# Kajtu_-DSP_digital_in.net
KiCad netlist of a schematic drawn in Altium Designer
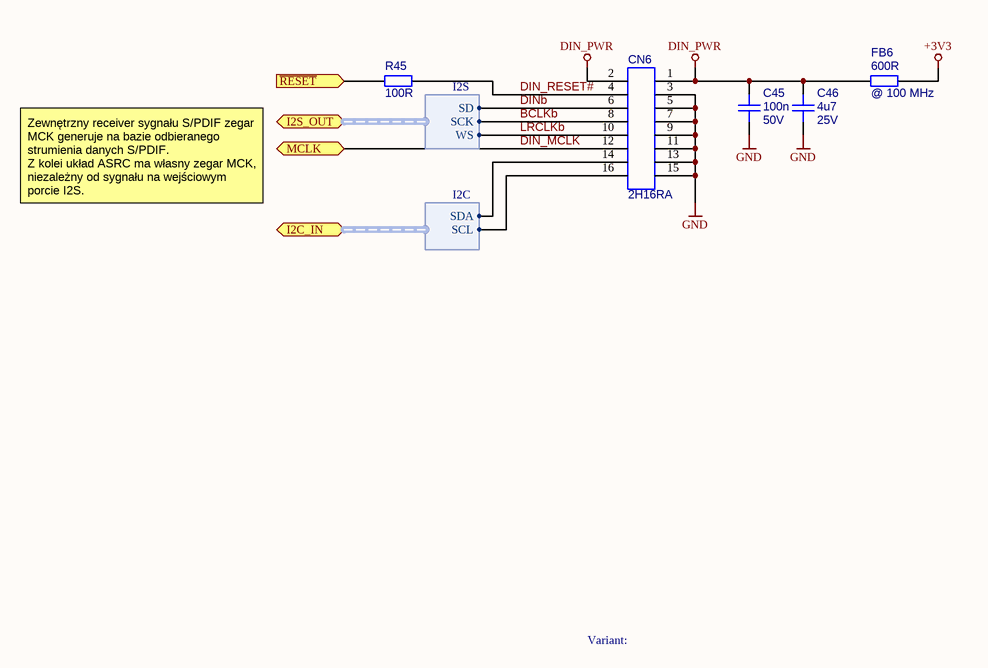
[diagram p0: Kajtuś-DSP_digital_in.SchDoc]

(export (version "E")
  (design (tool "Eeschema 10.0.6"))
  (components
    (comp (ref "C45")
      (value "100n")
      (footprint "C_0603_MA")
      (description "Kondensator ceramiczny SMD")
      (fields (field (name "PART NUMBER") "C_0603_100n_50V_X7R") (field (name "VOLTAGE") "50V"))
      (libsource (lib "AD_ostry_intlib") (part "C_0603_100n_50V_X7R"))
    )
    (comp (ref "C46")
      (value "4u7")
      (footprint "C_1206_MA")
      (description "Kondensator ceramiczny SMD")
      (fields
        (field (name "PART NUMBER") "C_1206_4u7_25V_X7R")
        (field (name "MANUFACTURER") "AVX, KEMET")
        (field (name "VOLTAGE") "25V")
      )
      (libsource (lib "AD_ostry_intlib") (part "C_1206_4u7_25V_X7R"))
    )
    (comp (ref "CN6")
      (value "2H16RA")
      (footprint "CN_2H16RA_WE_WR-PHD_61301621021")
      (description "Listwa kołkowa")
      (fields (field (name "PART NUMBER") "CN_2H16RA") (field (name "MANUFACTURER") "Ninigi"))
      (libsource (lib "AD_ostry_intlib") (part "CN_2H16RA"))
    )
    (comp (ref "FB6")
      (value "600R")
      (footprint "R_0603_MA")
      (description "Koralik ferrytowy")
      (fields
        (field (name "MANUFACTURER") "Yageo")
        (field (name "PART NUMBER") "FB_0603_PBY160808T-601Y_600R_1A")
        (field (name "@ FREQUENCY") "@ 100 MHz")
      )
      (libsource (lib "AD_ostry_intlib") (part "FB_0603_PBY160808T-601Y_600R_1A"))
    )
    (comp (ref "R45")
      (value "100R")
      (footprint "R_0603_MA")
      (description "Rezystor SMD")
      (fields (field (name "PART NUMBER") "R_0603_100R_5%") (field (name "MANUFACTURER") "Royal Ohm"))
      (libsource (lib "AD_ostry_intlib") (part "R_0603_100R_5%"))
    )
  )
  (nets
    (net (code "3") (name "+3V3") (class "Default")
      (node (ref "FB6") (pin "2") (pinfunction "2_2") (pintype "passive"))
    )
    (net (code "4") (name "/BCLKb") (class "Default")
      (node (ref "CN6") (pin "8") (pinfunction "8_8") (pintype "passive"))
    )
    (net (code "5") (name "/DIN_MCLK") (class "Default")
      (node (ref "CN6") (pin "12") (pinfunction "12_12") (pintype "passive"))
    )
    (net (code "6") (name "/DIN_RESET#") (class "Default")
      (node (ref "CN6") (pin "4") (pinfunction "4_4") (pintype "passive"))
      (node (ref "R45") (pin "2") (pinfunction "2_2") (pintype "passive"))
    )
    (net (code "7") (name "/DINb") (class "Default")
      (node (ref "CN6") (pin "6") (pinfunction "6_6") (pintype "passive"))
    )
    (net (code "8") (name "/LRCLKb") (class "Default")
      (node (ref "CN6") (pin "10") (pinfunction "10_10") (pintype "passive"))
    )
    (net (code "9") (name "/SCL") (class "Default")
      (node (ref "CN6") (pin "16") (pinfunction "16_16") (pintype "passive"))
    )
    (net (code "10") (name "/SDA") (class "Default")
      (node (ref "CN6") (pin "14") (pinfunction "14_14") (pintype "passive"))
    )
    (net (code "13") (name "/~{RESET}") (class "Default")
      (node (ref "R45") (pin "1") (pinfunction "1_1") (pintype "passive"))
    )
    (net (code "14") (name "DIN_PWR") (class "Default")
      (node (ref "C45") (pin "1") (pinfunction "1_1") (pintype "passive"))
      (node (ref "C46") (pin "1") (pinfunction "1_1") (pintype "passive"))
      (node (ref "CN6") (pin "1") (pinfunction "1_1") (pintype "passive"))
      (node (ref "CN6") (pin "2") (pinfunction "2_2") (pintype "passive"))
      (node (ref "FB6") (pin "1") (pinfunction "1_1") (pintype "passive"))
    )
    (net (code "15") (name "GND") (class "Default")
      (node (ref "C45") (pin "2") (pinfunction "2_2") (pintype "passive"))
      (node (ref "C46") (pin "2") (pinfunction "2_2") (pintype "passive"))
      (node (ref "CN6") (pin "11") (pinfunction "11_11") (pintype "passive"))
      (node (ref "CN6") (pin "13") (pinfunction "13_13") (pintype "passive"))
      (node (ref "CN6") (pin "15") (pinfunction "15_15") (pintype "passive"))
      (node (ref "CN6") (pin "3") (pinfunction "3_3") (pintype "passive"))
      (node (ref "CN6") (pin "5") (pinfunction "5_5") (pintype "passive"))
      (node (ref "CN6") (pin "7") (pinfunction "7_7") (pintype "passive"))
      (node (ref "CN6") (pin "9") (pinfunction "9_9") (pintype "passive"))
    )
  )
)
